# POWER.net
KiCad netlist of a schematic drawn in Altium Designer
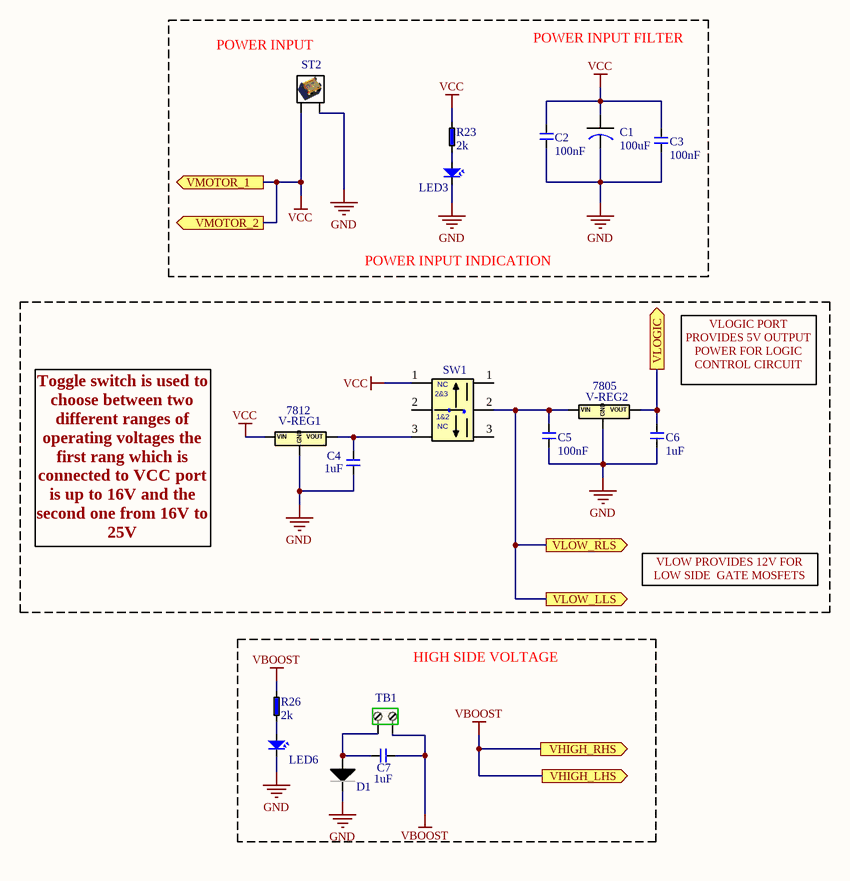
[diagram p0: POWER.SchDoc]

(export (version "E")
  (design (tool "Eeschema 10.0.6"))
  (components
    (comp (ref "C1")
      (value "100uF")
      (footprint "ECAP 5X11X2MM")
      (libsource (lib "Altium_Abbas") (part "CAP POL"))
    )
    (comp (ref "C2")
      (value "100nF")
      (footprint "CCAP 0.1 N Y")
      (libsource (lib "Altium_Abbas") (part "CERAMIC CAP"))
    )
    (comp (ref "C3")
      (value "100nF")
      (footprint "CCAP 0.1 N Y")
      (libsource (lib "Altium_Abbas") (part "CERAMIC CAP"))
    )
    (comp (ref "C4")
      (value "1uF")
      (footprint "CCAP 0.1 N Y")
      (libsource (lib "Altium_Abbas") (part "CERAMIC CAP"))
    )
    (comp (ref "C5")
      (value "100nF")
      (footprint "CCAP 0.1 N Y")
      (libsource (lib "Altium_Abbas") (part "CERAMIC CAP"))
    )
    (comp (ref "C6")
      (value "1uF")
      (footprint "CCAP 0.1 N Y")
      (libsource (lib "Altium_Abbas") (part "CERAMIC CAP"))
    )
    (comp (ref "C7")
      (value "1uF")
      (footprint "CCAP 0.1 N Y")
      (libsource (lib "Altium_Abbas") (part "CERAMIC CAP"))
    )
    (comp (ref "D1") (value "DIODE") (footprint "DIODE SMD") (libsource (lib "Altium_Abbas") (part "DIODE")))
    (comp (ref "LED3")
      (value "LED")
      (footprint "LED 3MM GREEN")
      (libsource (lib "Altium_Abbas") (part "LED"))
    )
    (comp (ref "LED6")
      (value "LED")
      (footprint "LED 5MM GREEN")
      (libsource (lib "Altium_Abbas") (part "LED"))
    )
    (comp (ref "R23")
      (value "2k")
      (footprint "RESISTOR _9")
      (libsource (lib "Altium_Abbas") (part "RESISTOR"))
    )
    (comp (ref "R26")
      (value "2k")
      (footprint "RESISTOR _9")
      (libsource (lib "Altium_Abbas") (part "RESISTOR"))
    )
    (comp (ref "ST2")
      (value "SCREW TERMINAL")
      (footprint "SCREW TERMINAL")
      (description "Barrier Terminal Block 2 Pin with cover 300V/25A")
      (libsource (lib "Altium_Abbas") (part "SCREW TERMINAL"))
    )
    (comp (ref "SW1")
      (value "Toggle Switch")
      (footprint "Toggle 3 pins")
      (description "Toggle Switch 3-Pin SPDT ON-ON 6A 125VAC")
      (libsource (lib "Altium_Abbas") (part "Toggle Switch"))
    )
    (comp (ref "TB1")
      (value "Terminal block 2 pin")
      (footprint "AK500/2 - pluggable")
      (description "Terminal Block 2 Pin 10A 300V")
      (libsource (lib "Altium_Abbas") (part "Terminal block 2 pin"))
    )
    (comp (ref "V-REG1")
      (value "7812")
      (footprint "V-REG")
      (description "78xx Regulators")
      (libsource (lib "Altium_Abbas") (part "V-REG"))
    )
    (comp (ref "V-REG2")
      (value "7805")
      (footprint "V-REG")
      (description "78xx Regulators")
      (libsource (lib "Altium_Abbas") (part "V-REG"))
    )
  )
  (nets
    (net (code "1") (name "/VLOGIC") (class "Default")
      (node (ref "C6") (pin "1") (pintype "passive"))
      (node (ref "V-REG2") (pin "3") (pinfunction "VOUT_3") (pintype "passive"))
    )
    (net (code "2") (name "/VLOW_LLS") (class "Default")
      (node (ref "C5") (pin "1") (pintype "passive"))
      (node (ref "SW1") (pin "2") (pinfunction "2_2") (pintype "passive"))
      (node (ref "V-REG2") (pin "1") (pinfunction "VIN_1") (pintype "passive"))
    )
    (net (code "3") (name "GND") (class "Default")
      (node (ref "C1") (pin "K") (pintype "passive"))
      (node (ref "C2") (pin "2") (pintype "passive"))
      (node (ref "C3") (pin "2") (pintype "passive"))
      (node (ref "C4") (pin "2") (pintype "passive"))
      (node (ref "C5") (pin "2") (pintype "passive"))
      (node (ref "C6") (pin "2") (pintype "passive"))
      (node (ref "D1") (pin "K") (pintype "passive"))
      (node (ref "LED3") (pin "K") (pintype "passive"))
      (node (ref "LED6") (pin "K") (pintype "passive"))
      (node (ref "ST2") (pin "2") (pinfunction "AC_2") (pintype "passive"))
      (node (ref "V-REG1") (pin "2") (pinfunction "GND_2") (pintype "passive"))
      (node (ref "V-REG2") (pin "2") (pinfunction "GND_2") (pintype "passive"))
    )
    (net (code "4") (name "Net-(C7-Pad1)") (class "Default")
      (node (ref "C7") (pin "1") (pintype "passive"))
      (node (ref "D1") (pin "A") (pintype "passive"))
      (node (ref "TB1") (pin "2") (pinfunction "*_2") (pintype "passive"))
    )
    (net (code "5") (name "Net-(R23-5)") (class "Default")
      (node (ref "LED3") (pin "A") (pintype "passive"))
      (node (ref "R23") (pin "1") (pinfunction "5_1") (pintype "passive"))
    )
    (net (code "6") (name "Net-(R26-5)") (class "Default")
      (node (ref "LED6") (pin "A") (pintype "passive"))
      (node (ref "R26") (pin "1") (pinfunction "5_1") (pintype "passive"))
    )
    (net (code "7") (name "Net-(V-REG1-VOUT)") (class "Default")
      (node (ref "C4") (pin "1") (pintype "passive"))
      (node (ref "SW1") (pin "3") (pinfunction "3_3") (pintype "passive"))
      (node (ref "V-REG1") (pin "3") (pinfunction "VOUT_3") (pintype "passive"))
    )
    (net (code "8") (name "VBOOST") (class "Default")
      (node (ref "C7") (pin "2") (pintype "passive"))
      (node (ref "R26") (pin "2") (pinfunction "6_2") (pintype "passive"))
      (node (ref "TB1") (pin "1") (pinfunction "*_1") (pintype "passive"))
    )
    (net (code "9") (name "VCC") (class "Default")
      (node (ref "C1") (pin "A") (pintype "passive"))
      (node (ref "C2") (pin "1") (pintype "passive"))
      (node (ref "C3") (pin "1") (pintype "passive"))
      (node (ref "R23") (pin "2") (pinfunction "6_2") (pintype "passive"))
      (node (ref "ST2") (pin "1") (pinfunction "AC_1") (pintype "passive"))
      (node (ref "SW1") (pin "1") (pinfunction "0_1") (pintype "passive"))
      (node (ref "V-REG1") (pin "1") (pinfunction "VIN_1") (pintype "passive"))
    )
    (net (code "10") (name "unconnected-(SW1-0-Pad1)") (class "Default")
      (node (ref "SW1") (pin "1") (pinfunction "0_1") (pintype "passive"))
    )
    (net (code "11") (name "unconnected-(SW1-Pad2)") (class "Default")
      (node (ref "SW1") (pin "2") (pinfunction "2_2") (pintype "passive"))
    )
    (net (code "12") (name "unconnected-(SW1-Pad3)") (class "Default")
      (node (ref "SW1") (pin "3") (pinfunction "3_3") (pintype "passive"))
    )
  )
)
